# RK3399_EDP_CSI_HDMI.net
KiCad netlist of a schematic drawn in Altium Designer
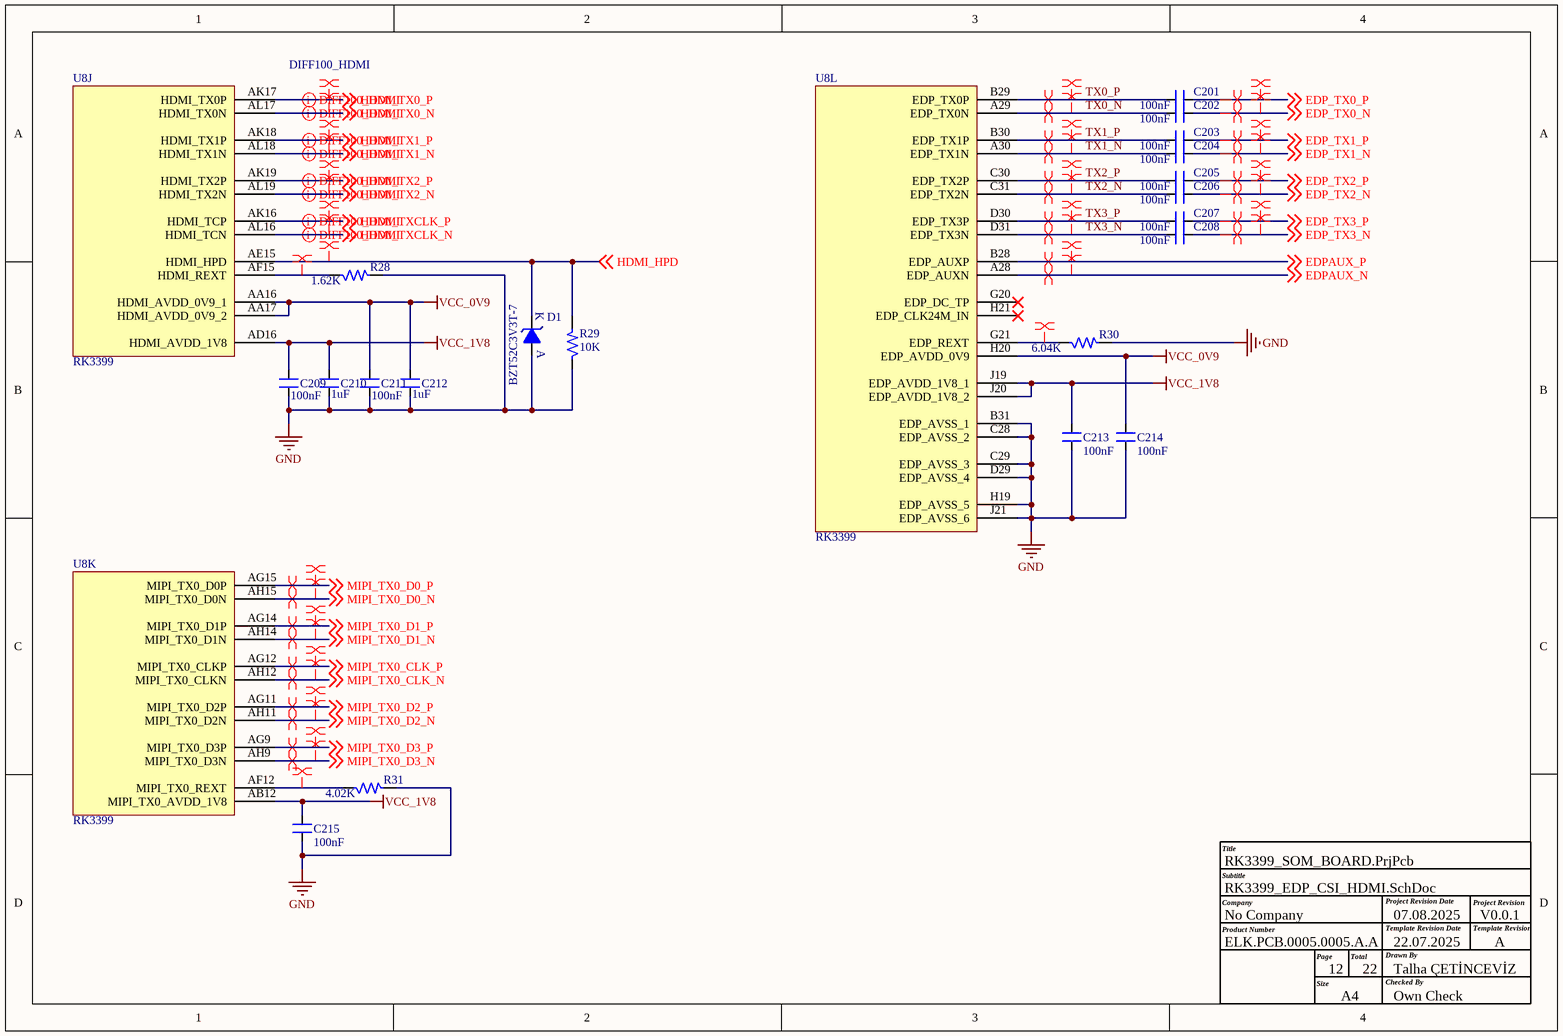
[diagram p0: RK3399_EDP_CSI_HDMI.SchDoc]

(export (version "E")
  (design (tool "Eeschema 10.0.6"))
  (components
    (comp (ref "C201")
      (value "100nF")
      (footprint "CAP_0201")
      (description "0.1µF ±10% 25V Ceramic Capacitor X5R 0201 (0603 Metric)")
      (fields
        (field (name "MANUFACTURER") "TDK Corporation")
        (field (name "MANUFACTURER PART NUMBER") "C0603X5R1E104K030BB")
      )
      (libsource (lib "EsteemPCB_SOM_Course_intlib") (part "CAP_100nF-25V-10%-0201"))
    )
    (comp (ref "C202")
      (value "100nF")
      (footprint "CAP_0201")
      (description "0.1µF ±10% 25V Ceramic Capacitor X5R 0201 (0603 Metric)")
      (fields
        (field (name "MANUFACTURER") "TDK Corporation")
        (field (name "MANUFACTURER PART NUMBER") "C0603X5R1E104K030BB")
      )
      (libsource (lib "EsteemPCB_SOM_Course_intlib") (part "CAP_100nF-25V-10%-0201"))
    )
    (comp (ref "C203")
      (value "100nF")
      (footprint "CAP_0201")
      (description "0.1µF ±10% 25V Ceramic Capacitor X5R 0201 (0603 Metric)")
      (fields
        (field (name "MANUFACTURER") "TDK Corporation")
        (field (name "MANUFACTURER PART NUMBER") "C0603X5R1E104K030BB")
      )
      (libsource (lib "EsteemPCB_SOM_Course_intlib") (part "CAP_100nF-25V-10%-0201"))
    )
    (comp (ref "C204")
      (value "100nF")
      (footprint "CAP_0201")
      (description "0.1µF ±10% 25V Ceramic Capacitor X5R 0201 (0603 Metric)")
      (fields
        (field (name "MANUFACTURER") "TDK Corporation")
        (field (name "MANUFACTURER PART NUMBER") "C0603X5R1E104K030BB")
      )
      (libsource (lib "EsteemPCB_SOM_Course_intlib") (part "CAP_100nF-25V-10%-0201"))
    )
    (comp (ref "C205")
      (value "100nF")
      (footprint "CAP_0201")
      (description "0.1µF ±10% 25V Ceramic Capacitor X5R 0201 (0603 Metric)")
      (fields
        (field (name "MANUFACTURER") "TDK Corporation")
        (field (name "MANUFACTURER PART NUMBER") "C0603X5R1E104K030BB")
      )
      (libsource (lib "EsteemPCB_SOM_Course_intlib") (part "CAP_100nF-25V-10%-0201"))
    )
    (comp (ref "C206")
      (value "100nF")
      (footprint "CAP_0201")
      (description "0.1µF ±10% 25V Ceramic Capacitor X5R 0201 (0603 Metric)")
      (fields
        (field (name "MANUFACTURER") "TDK Corporation")
        (field (name "MANUFACTURER PART NUMBER") "C0603X5R1E104K030BB")
      )
      (libsource (lib "EsteemPCB_SOM_Course_intlib") (part "CAP_100nF-25V-10%-0201"))
    )
    (comp (ref "C207")
      (value "100nF")
      (footprint "CAP_0201")
      (description "0.1µF ±10% 25V Ceramic Capacitor X5R 0201 (0603 Metric)")
      (fields
        (field (name "MANUFACTURER") "TDK Corporation")
        (field (name "MANUFACTURER PART NUMBER") "C0603X5R1E104K030BB")
      )
      (libsource (lib "EsteemPCB_SOM_Course_intlib") (part "CAP_100nF-25V-10%-0201"))
    )
    (comp (ref "C208")
      (value "100nF")
      (footprint "CAP_0201")
      (description "0.1µF ±10% 25V Ceramic Capacitor X5R 0201 (0603 Metric)")
      (fields
        (field (name "MANUFACTURER") "TDK Corporation")
        (field (name "MANUFACTURER PART NUMBER") "C0603X5R1E104K030BB")
      )
      (libsource (lib "EsteemPCB_SOM_Course_intlib") (part "CAP_100nF-25V-10%-0201"))
    )
    (comp (ref "C209")
      (value "100nF")
      (footprint "CAP_0201")
      (description "0.1µF ±10% 25V Ceramic Capacitor X5R 0201 (0603 Metric)")
      (fields
        (field (name "MANUFACTURER") "TDK Corporation")
        (field (name "MANUFACTURER PART NUMBER") "C0603X5R1E104K030BB")
      )
      (libsource (lib "EsteemPCB_SOM_Course_intlib") (part "CAP_100nF-25V-10%-0201"))
    )
    (comp (ref "C210")
      (value "1uF")
      (footprint "CAP_0201")
      (description "1µF ±20% 16V Ceramic Capacitor X5R 0201 (0603 Metric)")
      (fields
        (field (name "MANUFACTURER") "Samsung Electro-Mechanics")
        (field (name "MANUFACTURER PART NUMBER") "CL03A105MO3NRNH")
      )
      (libsource (lib "EsteemPCB_SOM_Course_intlib") (part "CAP_1uF-16V-10%-0201"))
    )
    (comp (ref "C211")
      (value "100nF")
      (footprint "CAP_0201")
      (description "0.1µF ±10% 25V Ceramic Capacitor X5R 0201 (0603 Metric)")
      (fields
        (field (name "MANUFACTURER") "TDK Corporation")
        (field (name "MANUFACTURER PART NUMBER") "C0603X5R1E104K030BB")
      )
      (libsource (lib "EsteemPCB_SOM_Course_intlib") (part "CAP_100nF-25V-10%-0201"))
    )
    (comp (ref "C212")
      (value "1uF")
      (footprint "CAP_0201")
      (description "1µF ±20% 16V Ceramic Capacitor X5R 0201 (0603 Metric)")
      (fields
        (field (name "MANUFACTURER") "Samsung Electro-Mechanics")
        (field (name "MANUFACTURER PART NUMBER") "CL03A105MO3NRNH")
      )
      (libsource (lib "EsteemPCB_SOM_Course_intlib") (part "CAP_1uF-16V-10%-0201"))
    )
    (comp (ref "C213")
      (value "100nF")
      (footprint "CAP_0201")
      (description "0.1µF ±10% 25V Ceramic Capacitor X5R 0201 (0603 Metric)")
      (fields
        (field (name "MANUFACTURER") "TDK Corporation")
        (field (name "MANUFACTURER PART NUMBER") "C0603X5R1E104K030BB")
      )
      (libsource (lib "EsteemPCB_SOM_Course_intlib") (part "CAP_100nF-25V-10%-0201"))
    )
    (comp (ref "C214")
      (value "100nF")
      (footprint "CAP_0201")
      (description "0.1µF ±10% 25V Ceramic Capacitor X5R 0201 (0603 Metric)")
      (fields
        (field (name "MANUFACTURER") "TDK Corporation")
        (field (name "MANUFACTURER PART NUMBER") "C0603X5R1E104K030BB")
      )
      (libsource (lib "EsteemPCB_SOM_Course_intlib") (part "CAP_100nF-25V-10%-0201"))
    )
    (comp (ref "C215")
      (value "100nF")
      (footprint "CAP_0201")
      (description "0.1µF ±10% 25V Ceramic Capacitor X5R 0201 (0603 Metric)")
      (fields
        (field (name "MANUFACTURER") "TDK Corporation")
        (field (name "MANUFACTURER PART NUMBER") "C0603X5R1E104K030BB")
      )
      (libsource (lib "EsteemPCB_SOM_Course_intlib") (part "CAP_100nF-25V-10%-0201"))
    )
    (comp (ref "D1")
      (value "BZT52C3V3T-7")
      (footprint "DIO_SOD523")
      (description "Zener Diode 3.3V 300mW ±6% Surface Mount SOD-523")
      (fields (field (name "MANUFACTURER") "Diodes Incorporated"))
      (libsource (lib "EsteemPCB_SOM_Course_intlib") (part "DIO-Z_3.3V-300mW-SOD-523"))
    )
    (comp (ref "R28")
      (value "1.62K")
      (footprint "RES_0201")
      (description "1.62 kOhms ±1% 0.05W, 1/20W Chip Resistor 0201 (0603 Metric) Automotive AEC-Q200 Thick Film")
      (fields
        (field (name "MANUFACTURER") "Panasonic Electronic Components")
        (field (name "MANUFACTURER PART NUMBER") "ERJ-1GNF1621C")
      )
      (libsource (lib "EsteemPCB_SOM_Course_intlib") (part "RES_1.62K-0.05W-1%-0201"))
    )
    (comp (ref "R29")
      (value "10K")
      (footprint "RES_0201")
      (description "10 kOhms ±1% 0.05W, 1/20W Chip Resistor 0201 (0603 Metric) Thick Film")
      (fields
        (field (name "MANUFACTURER") "Stackpole Electronics Inc")
        (field (name "MANUFACTURER PART NUMBER") "RMCF0201FT10K0")
      )
      (libsource (lib "EsteemPCB_SOM_Course_intlib") (part "RES_10K-0.05W-1%-0201"))
    )
    (comp (ref "R30")
      (value "6.04K")
      (footprint "RES_0201")
      (description "6.04 kOhms ±1% 0.05W, 1/20W Chip Resistor 0201 (0603 Metric) Thick Film")
      (fields
        (field (name "MANUFACTURER") "Panasonic Electronic Components")
        (field (name "MANUFACTURER PART NUMBER") "ERJ-1GEF6041C")
      )
      (libsource (lib "EsteemPCB_SOM_Course_intlib") (part "RES_6.04K-0.05W-1%-0201"))
    )
    (comp (ref "R31")
      (value "4.02K")
      (footprint "RES_0201")
      (description "4.02 kOhms ±1% 0.05W, 1/20W Chip Resistor 0201 (0603 Metric) Thick Film")
      (fields
        (field (name "MANUFACTURER") "Yageo")
        (field (name "MANUFACTURER PART NUMBER") "RC0201FR-074K02L")
      )
      (libsource (lib "EsteemPCB_SOM_Course_intlib") (part "RES_4.02K-0.05W-1%-0201"))
    )
    (comp (ref "U8")
      (value "RK3399")
      (footprint "FBGA828_23_826X826")
      (description "RK3399 is a low power, high performance processor for computing, personal mobile.")
      (fields (field (name "MANUFACTURER") "Rockchip"))
      (libsource (lib "") (part "IC_RK3399-FCBGA828_1"))
    )
  )
  (nets
    (net (code "1") (name "/TX0_N") (class "Default")
      (node (ref "C202") (pin "1") (pinfunction "1_1") (pintype "passive"))
      (node (ref "U8") (pin "A29") (pinfunction "EDP_TX0N_A29") (pintype "passive"))
    )
    (net (code "2") (name "/TX0_P") (class "Default")
      (node (ref "C201") (pin "1") (pinfunction "1_1") (pintype "passive"))
      (node (ref "U8") (pin "B29") (pinfunction "EDP_TX0P_B29") (pintype "passive"))
    )
    (net (code "3") (name "/TX1_N") (class "Default")
      (node (ref "C204") (pin "1") (pinfunction "1_1") (pintype "passive"))
      (node (ref "U8") (pin "A30") (pinfunction "EDP_TX1N_A30") (pintype "passive"))
    )
    (net (code "4") (name "/TX1_P") (class "Default")
      (node (ref "C203") (pin "1") (pinfunction "1_1") (pintype "passive"))
      (node (ref "U8") (pin "B30") (pinfunction "EDP_TX1P_B30") (pintype "passive"))
    )
    (net (code "5") (name "/TX2_N") (class "Default")
      (node (ref "C206") (pin "1") (pinfunction "1_1") (pintype "passive"))
      (node (ref "U8") (pin "C31") (pinfunction "EDP_TX2N_C31") (pintype "passive"))
    )
    (net (code "6") (name "/TX2_P") (class "Default")
      (node (ref "C205") (pin "1") (pinfunction "1_1") (pintype "passive"))
      (node (ref "U8") (pin "C30") (pinfunction "EDP_TX2P_C30") (pintype "passive"))
    )
    (net (code "7") (name "/TX3_N") (class "Default")
      (node (ref "C208") (pin "1") (pinfunction "1_1") (pintype "passive"))
      (node (ref "U8") (pin "D31") (pinfunction "EDP_TX3N_D31") (pintype "passive"))
    )
    (net (code "8") (name "/TX3_P") (class "Default")
      (node (ref "C207") (pin "1") (pinfunction "1_1") (pintype "passive"))
      (node (ref "U8") (pin "D30") (pinfunction "EDP_TX3P_D30") (pintype "passive"))
    )
    (net (code "9") (name "EDPAUX_N") (class "Default")
      (node (ref "U8") (pin "A28") (pinfunction "EDP_AUXN_A28") (pintype "passive"))
    )
    (net (code "10") (name "EDPAUX_P") (class "Default")
      (node (ref "U8") (pin "B28") (pinfunction "EDP_AUXP_B28") (pintype "passive"))
    )
    (net (code "11") (name "EDP_TX0_N") (class "Default")
      (node (ref "C202") (pin "2") (pinfunction "2_2") (pintype "passive"))
    )
    (net (code "12") (name "EDP_TX0_P") (class "Default")
      (node (ref "C201") (pin "2") (pinfunction "2_2") (pintype "passive"))
    )
    (net (code "13") (name "EDP_TX1_N") (class "Default")
      (node (ref "C204") (pin "2") (pinfunction "2_2") (pintype "passive"))
    )
    (net (code "14") (name "EDP_TX1_P") (class "Default")
      (node (ref "C203") (pin "2") (pinfunction "2_2") (pintype "passive"))
    )
    (net (code "15") (name "EDP_TX2_N") (class "Default")
      (node (ref "C206") (pin "2") (pinfunction "2_2") (pintype "passive"))
    )
    (net (code "16") (name "EDP_TX2_P") (class "Default")
      (node (ref "C205") (pin "2") (pinfunction "2_2") (pintype "passive"))
    )
    (net (code "17") (name "EDP_TX3_N") (class "Default")
      (node (ref "C208") (pin "2") (pinfunction "2_2") (pintype "passive"))
    )
    (net (code "18") (name "EDP_TX3_P") (class "Default")
      (node (ref "C207") (pin "2") (pinfunction "2_2") (pintype "passive"))
    )
    (net (code "19") (name "GND") (class "Default")
      (node (ref "C209") (pin "1") (pinfunction "1_1") (pintype "passive"))
      (node (ref "C210") (pin "1") (pinfunction "1_1") (pintype "passive"))
      (node (ref "C211") (pin "1") (pinfunction "1_1") (pintype "passive"))
      (node (ref "C212") (pin "1") (pinfunction "1_1") (pintype "passive"))
      (node (ref "C213") (pin "1") (pinfunction "1_1") (pintype "passive"))
      (node (ref "C214") (pin "1") (pinfunction "1_1") (pintype "passive"))
      (node (ref "C215") (pin "1") (pinfunction "1_1") (pintype "passive"))
      (node (ref "D1") (pin "A") (pinfunction "A_A") (pintype "passive"))
      (node (ref "R28") (pin "2") (pinfunction "2_2") (pintype "passive"))
      (node (ref "R29") (pin "1") (pinfunction "1_1") (pintype "passive"))
      (node (ref "R30") (pin "2") (pinfunction "2_2") (pintype "passive"))
      (node (ref "R31") (pin "2") (pinfunction "2_2") (pintype "passive"))
      (node (ref "U8") (pin "B31") (pinfunction "EDP_AVSS_1_B31") (pintype "passive"))
      (node (ref "U8") (pin "C28") (pinfunction "EDP_AVSS_2_C28") (pintype "passive"))
      (node (ref "U8") (pin "C29") (pinfunction "EDP_AVSS_3_C29") (pintype "passive"))
      (node (ref "U8") (pin "D29") (pinfunction "EDP_AVSS_4_D29") (pintype "passive"))
      (node (ref "U8") (pin "H19") (pinfunction "EDP_AVSS_5_H19") (pintype "passive"))
      (node (ref "U8") (pin "J21") (pinfunction "EDP_AVSS_6_J21") (pintype "passive"))
    )
    (net (code "20") (name "HDMI_HPD") (class "Default")
      (node (ref "D1") (pin "K") (pinfunction "K_K") (pintype "passive"))
      (node (ref "R29") (pin "2") (pinfunction "2_2") (pintype "passive"))
      (node (ref "U8") (pin "AE15") (pinfunction "HDMI_HPD_AE15") (pintype "passive"))
    )
    (net (code "21") (name "HDMI_TX0_N") (class "Default")
      (node (ref "U8") (pin "AL17") (pinfunction "HDMI_TX0N_AL17") (pintype "passive"))
    )
    (net (code "22") (name "HDMI_TX0_P") (class "Default")
      (node (ref "U8") (pin "AK17") (pinfunction "HDMI_TX0P_AK17") (pintype "passive"))
    )
    (net (code "23") (name "HDMI_TX1_N") (class "Default")
      (node (ref "U8") (pin "AL18") (pinfunction "HDMI_TX1N_AL18") (pintype "passive"))
    )
    (net (code "24") (name "HDMI_TX1_P") (class "Default")
      (node (ref "U8") (pin "AK18") (pinfunction "HDMI_TX1P_AK18") (pintype "passive"))
    )
    (net (code "25") (name "HDMI_TX2_N") (class "Default")
      (node (ref "U8") (pin "AL19") (pinfunction "HDMI_TX2N_AL19") (pintype "passive"))
    )
    (net (code "26") (name "HDMI_TX2_P") (class "Default")
      (node (ref "U8") (pin "AK19") (pinfunction "HDMI_TX2P_AK19") (pintype "passive"))
    )
    (net (code "27") (name "HDMI_TXCLK_N") (class "Default")
      (node (ref "U8") (pin "AL16") (pinfunction "HDMI_TCN_AL16") (pintype "passive"))
    )
    (net (code "28") (name "HDMI_TXCLK_P") (class "Default")
      (node (ref "U8") (pin "AK16") (pinfunction "HDMI_TCP_AK16") (pintype "passive"))
    )
    (net (code "29") (name "MIPI_TX0_CLK_N") (class "Default")
      (node (ref "U8") (pin "AH12") (pinfunction "MIPI_TX0_CLKN_AH12") (pintype "passive"))
    )
    (net (code "30") (name "MIPI_TX0_CLK_P") (class "Default")
      (node (ref "U8") (pin "AG12") (pinfunction "MIPI_TX0_CLKP_AG12") (pintype "passive"))
    )
    (net (code "31") (name "MIPI_TX0_D0_N") (class "Default")
      (node (ref "U8") (pin "AH15") (pinfunction "MIPI_TX0_D0N_AH15") (pintype "passive"))
    )
    (net (code "32") (name "MIPI_TX0_D0_P") (class "Default")
      (node (ref "U8") (pin "AG15") (pinfunction "MIPI_TX0_D0P_AG15") (pintype "passive"))
    )
    (net (code "33") (name "MIPI_TX0_D1_N") (class "Default")
      (node (ref "U8") (pin "AH14") (pinfunction "MIPI_TX0_D1N_AH14") (pintype "passive"))
    )
    (net (code "34") (name "MIPI_TX0_D1_P") (class "Default")
      (node (ref "U8") (pin "AG14") (pinfunction "MIPI_TX0_D1P_AG14") (pintype "passive"))
    )
    (net (code "35") (name "MIPI_TX0_D2_N") (class "Default")
      (node (ref "U8") (pin "AH11") (pinfunction "MIPI_TX0_D2N_AH11") (pintype "passive"))
    )
    (net (code "36") (name "MIPI_TX0_D2_P") (class "Default")
      (node (ref "U8") (pin "AG11") (pinfunction "MIPI_TX0_D2P_AG11") (pintype "passive"))
    )
    (net (code "37") (name "MIPI_TX0_D3_N") (class "Default")
      (node (ref "U8") (pin "AH9") (pinfunction "MIPI_TX0_D3N_AH9") (pintype "passive"))
    )
    (net (code "38") (name "MIPI_TX0_D3_P") (class "Default")
      (node (ref "U8") (pin "AG9") (pinfunction "MIPI_TX0_D3P_AG9") (pintype "passive"))
    )
    (net (code "39") (name "Net-(U8J-HDMI_REXT)") (class "Default")
      (node (ref "R28") (pin "1") (pinfunction "1_1") (pintype "passive"))
      (node (ref "U8") (pin "AF15") (pinfunction "HDMI_REXT_AF15") (pintype "passive"))
    )
    (net (code "40") (name "Net-(U8K-MIPI_TX0_REXT)") (class "Default")
      (node (ref "R31") (pin "1") (pinfunction "1_1") (pintype "passive"))
      (node (ref "U8") (pin "AF12") (pinfunction "MIPI_TX0_REXT_AF12") (pintype "passive"))
    )
    (net (code "41") (name "Net-(U8L-EDP_REXT)") (class "Default")
      (node (ref "R30") (pin "1") (pinfunction "1_1") (pintype "passive"))
      (node (ref "U8") (pin "G21") (pinfunction "EDP_REXT_G21") (pintype "passive"))
    )
    (net (code "42") (name "VCC_0V9") (class "Default")
      (node (ref "C211") (pin "2") (pinfunction "2_2") (pintype "passive"))
      (node (ref "C212") (pin "2") (pinfunction "2_2") (pintype "passive"))
      (node (ref "C214") (pin "2") (pinfunction "2_2") (pintype "passive"))
      (node (ref "U8") (pin "AA16") (pinfunction "HDMI_AVDD_0V9_1_AA16") (pintype "passive"))
      (node (ref "U8") (pin "AA17") (pinfunction "HDMI_AVDD_0V9_2_AA17") (pintype "passive"))
      (node (ref "U8") (pin "H20") (pinfunction "EDP_AVDD_0V9_H20") (pintype "passive"))
    )
    (net (code "43") (name "VCC_1V8") (class "Default")
      (node (ref "C209") (pin "2") (pinfunction "2_2") (pintype "passive"))
      (node (ref "C210") (pin "2") (pinfunction "2_2") (pintype "passive"))
      (node (ref "C213") (pin "2") (pinfunction "2_2") (pintype "passive"))
      (node (ref "C215") (pin "2") (pinfunction "2_2") (pintype "passive"))
      (node (ref "U8") (pin "AB12") (pinfunction "MIPI_TX0_AVDD_1V8_AB12") (pintype "passive"))
      (node (ref "U8") (pin "AD16") (pinfunction "HDMI_AVDD_1V8_AD16") (pintype "passive"))
      (node (ref "U8") (pin "J19") (pinfunction "EDP_AVDD_1V8_1_J19") (pintype "passive"))
      (node (ref "U8") (pin "J20") (pinfunction "EDP_AVDD_1V8_2_J20") (pintype "passive"))
    )
    (net (code "44") (name "unconnected-(U8L-EDP_CLK24M_IN-PadH21)") (class "Default")
      (node (ref "U8") (pin "H21") (pinfunction "EDP_CLK24M_IN_H21") (pintype "passive+no_connect"))
    )
    (net (code "45") (name "unconnected-(U8L-EDP_DC_TP-PadG20)") (class "Default")
      (node (ref "U8") (pin "G20") (pinfunction "EDP_DC_TP_G20") (pintype "passive+no_connect"))
    )
  )
)
